# Arduino___case01.net
KiCad netlist of a schematic drawn in Altium Designer
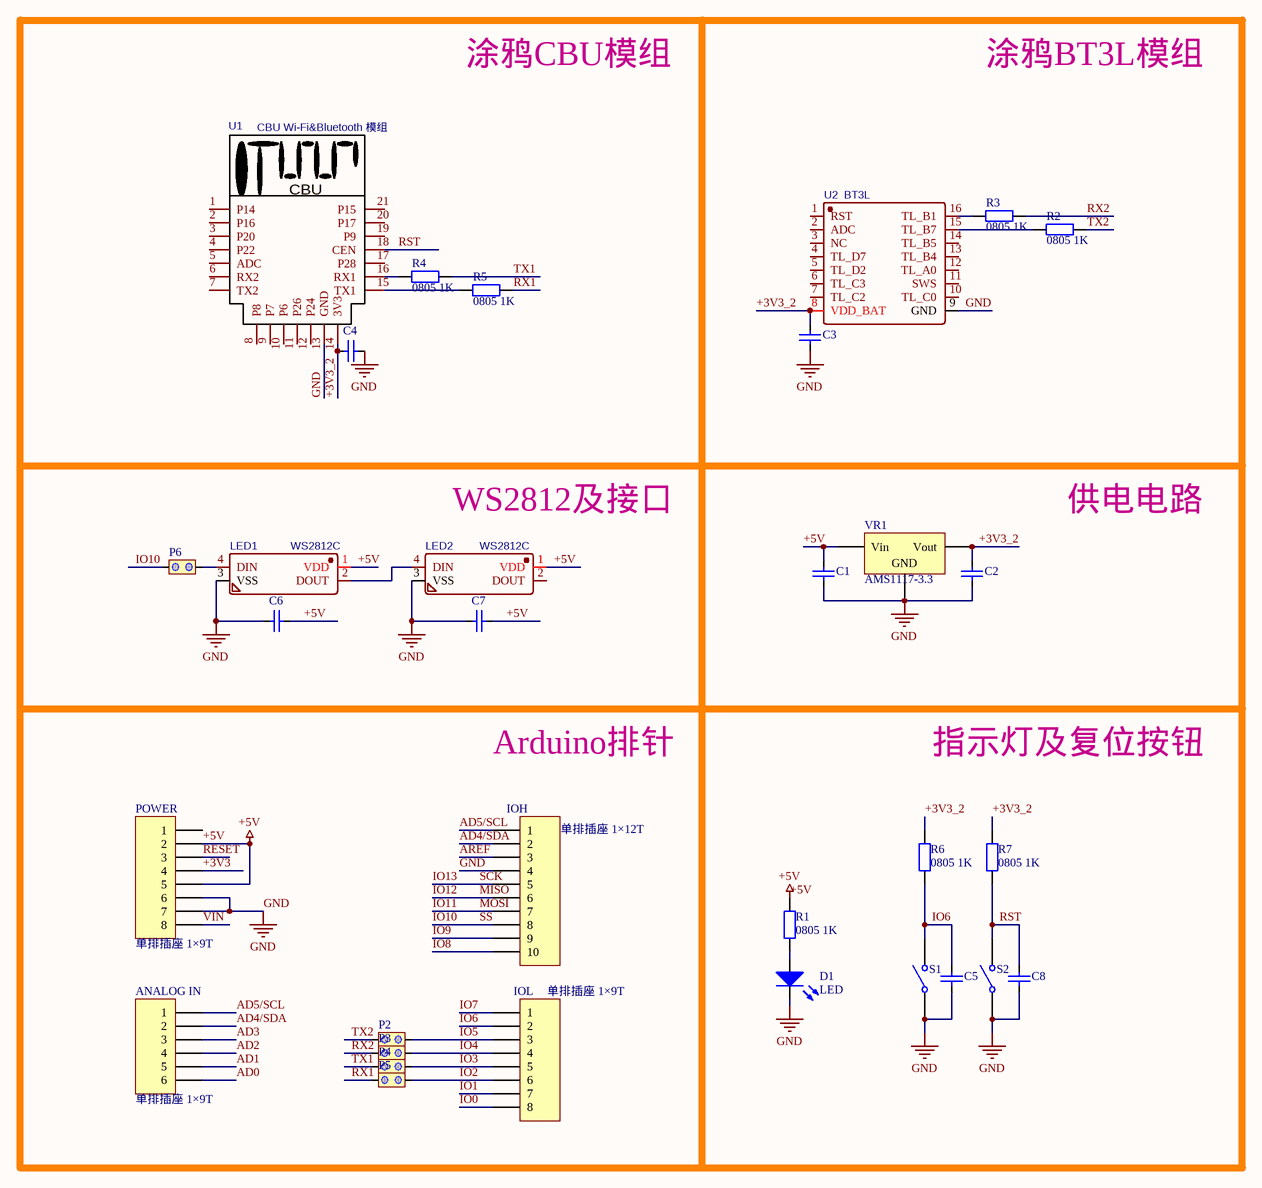
[diagram p0: Arduino_三明治开发板_case01.SchDoc]

(export (version "E")
  (design (tool "Eeschema 10.0.6"))
  (components
    (comp (ref "ANALOG IN")
      (value "单排插座 1×9T")
      (footprint "HDR1X6Z")
      (description "Header, 6-Pin")
      (fields (field (name "PUBLISHER") "Altium Limited"))
      (libsource (lib "Miscellaneous Connectors") (part "Header 6"))
    )
    (comp (ref "C1")
      (value "1206 0.1uF")
      (footprint "PcbLib1:0805-CAP-min")
      (description "Capacitor")
      (fields (field (name "PUBLISHER") "Altium Limited"))
      (libsource (lib "Cap_han") (part "Cap-1206"))
    )
    (comp (ref "C2")
      (value "1206 0.1uF")
      (footprint "PcbLib1:0805-CAP-min")
      (description "Capacitor")
      (fields (field (name "PUBLISHER") "Altium Limited"))
      (libsource (lib "Cap_han") (part "Cap-1206"))
    )
    (comp (ref "C3")
      (value "1206 0.1uF")
      (footprint "0805-CAP-min")
      (description "Capacitor")
      (fields (field (name "PUBLISHER") "Altium Limited"))
      (libsource (lib "Cap_han") (part "Cap-1206"))
    )
    (comp (ref "C4")
      (value "1206 0.1uF")
      (footprint "PcbLib1:0805-CAP-min")
      (description "Capacitor")
      (fields (field (name "PUBLISHER") "Altium Limited"))
      (libsource (lib "Cap_han") (part "Cap-1206"))
    )
    (comp (ref "C5")
      (value "1206 0.1uF")
      (footprint "PcbLib1:0805-CAP-min")
      (description "Capacitor")
      (fields (field (name "PUBLISHER") "Altium Limited"))
      (libsource (lib "Cap_han") (part "Cap-1206"))
    )
    (comp (ref "C6")
      (value "1206 0.1uF")
      (footprint "PcbLib1:0805-CAP-min")
      (description "Capacitor")
      (fields (field (name "PUBLISHER") "Altium Limited"))
      (libsource (lib "Cap_han") (part "Cap-1206"))
    )
    (comp (ref "C7")
      (value "1206 0.1uF")
      (footprint "PcbLib1:0805-CAP-min")
      (description "Capacitor")
      (fields (field (name "PUBLISHER") "Altium Limited"))
      (libsource (lib "Cap_han") (part "Cap-1206"))
    )
    (comp (ref "C8")
      (value "1206 0.1uF")
      (footprint "PcbLib1:0805-CAP-min")
      (description "Capacitor")
      (fields (field (name "PUBLISHER") "Altium Limited"))
      (libsource (lib "Cap_han") (part "Cap-1206"))
    )
    (comp (ref "D1")
      (value "LED")
      (footprint "PcbLib1:LED3014-FD")
      (fields (field (name "PUBLISHER") "Altium Limited"))
      (libsource (lib "LED_han") (part "LED-3014"))
    )
    (comp (ref "IOH")
      (value "单排插座 1×12T")
      (footprint "HDR1X10Z")
      (description "Header, 10-Pin")
      (fields (field (name "PUBLISHER") "Altium Limited"))
      (libsource (lib "Miscellaneous Connectors") (part "Header 10"))
    )
    (comp (ref "IOL")
      (value "单排插座 1×9T")
      (footprint "HDR1X8Z")
      (description "Header, 8-Pin")
      (fields (field (name "PUBLISHER") "Altium Limited"))
      (libsource (lib "Miscellaneous Connectors") (part "Header 8"))
    )
    (comp (ref "LED1")
      (value "WS2812C")
      (footprint "LED-SMD_4P-L5.0-W5.0-TL")
      (fields (field (name "BOM_SUPPLIER PART") "C114587") (field (name "CONTRIBUTOR") "LCSC"))
      (libsource (lib "altium-import") (part "root_2_WS2812C_"))
    )
    (comp (ref "LED2")
      (value "WS2812C")
      (footprint "LED-SMD_4P-L5.0-W5.0-TL")
      (fields (field (name "BOM_SUPPLIER PART") "C114587") (field (name "CONTRIBUTOR") "LCSC"))
      (libsource (lib "altium-import") (part "root_2_WS2812C_"))
    )
    (comp (ref "P2")
      (value "HDR1*2")
      (footprint "HDR1X2")
      (fields (field (name "PUBLISHER") "Altium Limited"))
      (libsource (lib "Connectors_han") (part "HDR1*2_2"))
    )
    (comp (ref "P3")
      (value "HDR1*2")
      (footprint "HDR1X2")
      (fields (field (name "PUBLISHER") "Altium Limited"))
      (libsource (lib "Connectors_han") (part "HDR1*2_2"))
    )
    (comp (ref "P4")
      (value "HDR1*2")
      (footprint "HDR1X2")
      (fields (field (name "PUBLISHER") "Altium Limited"))
      (libsource (lib "Connectors_han") (part "HDR1*2_2"))
    )
    (comp (ref "P5")
      (value "HDR1*2")
      (footprint "HDR1X2")
      (fields (field (name "PUBLISHER") "Altium Limited"))
      (libsource (lib "Connectors_han") (part "HDR1*2_2"))
    )
    (comp (ref "P6")
      (value "HDR1*2")
      (footprint "HDR1X2")
      (fields (field (name "PUBLISHER") "Altium Limited"))
      (libsource (lib "Connectors_han") (part "HDR1*2_2"))
    )
    (comp (ref "POWER")
      (value "单排插座 1×9T")
      (footprint "HDR1X8Z")
      (description "Header, 8-Pin")
      (fields (field (name "PUBLISHER") "Altium Limited"))
      (libsource (lib "") (part "Header 8_1"))
    )
    (comp (ref "R1")
      (value "0805 1K")
      (footprint "0805-R-min")
      (description "Resistor")
      (fields (field (name "PUBLISHER") "Altium Limited"))
      (libsource (lib "Resistance_han") (part "Res-0805"))
    )
    (comp (ref "R2")
      (value "0805 1K")
      (footprint "0805-R-min")
      (description "Resistor")
      (fields (field (name "PUBLISHER") "Altium Limited"))
      (libsource (lib "") (part "Res-0805_1"))
    )
    (comp (ref "R3")
      (value "0805 1K")
      (footprint "0805-R-min")
      (description "Resistor")
      (fields (field (name "PUBLISHER") "Altium Limited"))
      (libsource (lib "") (part "Res-0805_1"))
    )
    (comp (ref "R4")
      (value "0805 1K")
      (footprint "0805-R-min")
      (description "Resistor")
      (fields (field (name "PUBLISHER") "Altium Limited"))
      (libsource (lib "") (part "Res-0805_1"))
    )
    (comp (ref "R5")
      (value "0805 1K")
      (footprint "0805-R-min")
      (description "Resistor")
      (fields (field (name "PUBLISHER") "Altium Limited"))
      (libsource (lib "") (part "Res-0805_1"))
    )
    (comp (ref "R6")
      (value "0805 1K")
      (footprint "0805-R-min")
      (description "Resistor")
      (fields (field (name "PUBLISHER") "Altium Limited"))
      (libsource (lib "Resistance_han") (part "Res-0805"))
    )
    (comp (ref "R7")
      (value "0805 1K")
      (footprint "0805-R-min")
      (description "Resistor")
      (fields (field (name "PUBLISHER") "Altium Limited"))
      (libsource (lib "Resistance_han") (part "Res-0805"))
    )
    (comp (ref "S1")
      (value "SW-SPST")
      (footprint "Switch")
      (description "Single-Pole, Single-Throw Switch")
      (fields (field (name "PUBLISHER") "Altium Limited"))
      (libsource (lib "Miscellaneous Devices") (part "SW-SPST"))
    )
    (comp (ref "S2")
      (value "SW-SPST")
      (footprint "Switch")
      (description "Single-Pole, Single-Throw Switch")
      (fields (field (name "PUBLISHER") "Altium Limited"))
      (libsource (lib "Miscellaneous Devices") (part "SW-SPST"))
    )
    (comp (ref "U1")
      (value "CBU Wi-Fi&Bluetooth 模组")
      (footprint "PcbLib1:CBU WIFI&BLUETOOTH")
      (fields (field (name "BOM_MANUFACTURER PART") "SHOWNAME=F") (field (name "CONTRIBUTOR") "chenlf"))
      (libsource (lib "MCU_han") (part "CBU Wi-Fi&Bluetooth 模组"))
    )
    (comp (ref "U2")
      (value "BT3L")
      (footprint "PcbLib1:BLUETOOTH-SMD_16P-L24.0-W16.0-P2.0-BT3L")
      (fields (field (name "BOM_SUPPLIER PART") "C2828287") (field (name "CONTRIBUTOR") "LCSC"))
      (libsource (lib "altium-import") (part "root_0_mirrored_BT3L_"))
    )
    (comp (ref "VR1")
      (value "AMS1117-3.3")
      (footprint "SOT-223")
      (description "低压差线性稳压(LDO)")
      (libsource (lib "LDO") (part "SOT-223 AMS1117-3.3"))
    )
  )
  (nets
    (net (code "1") (name "+5V") (class "Default")
      (node (ref "C1") (pin "1") (pinfunction "1_1") (pintype "passive"))
      (node (ref "C6") (pin "1") (pinfunction "1_1") (pintype "passive"))
      (node (ref "C7") (pin "1") (pinfunction "1_1") (pintype "passive"))
      (node (ref "LED1") (pin "1") (pinfunction "VDD_1") (pintype "passive"))
      (node (ref "LED2") (pin "1") (pinfunction "VDD_1") (pintype "passive"))
      (node (ref "POWER") (pin "2") (pinfunction "2_2") (pintype "passive"))
      (node (ref "POWER") (pin "5") (pinfunction "5_5") (pintype "passive"))
      (node (ref "R1") (pin "1") (pinfunction "1_1") (pintype "passive"))
      (node (ref "VR1") (pin "3") (pinfunction "Vin_3") (pintype "passive"))
    )
    (net (code "2") (name "/+3V3") (class "Default")
      (node (ref "POWER") (pin "4") (pinfunction "4_4") (pintype "passive"))
    )
    (net (code "3") (name "/+3V3_2") (class "Default")
      (node (ref "C2") (pin "2") (pinfunction "2_2") (pintype "passive"))
      (node (ref "C3") (pin "2") (pinfunction "2_2") (pintype "passive"))
      (node (ref "C4") (pin "2") (pinfunction "2_2") (pintype "passive"))
      (node (ref "R6") (pin "1") (pinfunction "1_1") (pintype "passive"))
      (node (ref "R7") (pin "1") (pinfunction "1_1") (pintype "passive"))
      (node (ref "U1") (pin "14") (pinfunction "3V3_14") (pintype "passive"))
      (node (ref "U2") (pin "8") (pinfunction "VDD_BAT_8") (pintype "passive"))
      (node (ref "VR1") (pin "2") (pinfunction "Vout_2") (pintype "passive"))
    )
    (net (code "4") (name "/AD0") (class "Default")
      (node (ref "ANALOG IN") (pin "6") (pinfunction "6_6") (pintype "passive"))
    )
    (net (code "5") (name "/AD1") (class "Default")
      (node (ref "ANALOG IN") (pin "5") (pinfunction "5_5") (pintype "passive"))
    )
    (net (code "6") (name "/AD2") (class "Default")
      (node (ref "ANALOG IN") (pin "4") (pinfunction "4_4") (pintype "passive"))
    )
    (net (code "7") (name "/AD3") (class "Default")
      (node (ref "ANALOG IN") (pin "3") (pinfunction "3_3") (pintype "passive"))
    )
    (net (code "8") (name "/AD4{slash}SDA") (class "Default")
      (node (ref "ANALOG IN") (pin "2") (pinfunction "2_2") (pintype "passive"))
      (node (ref "IOH") (pin "2") (pinfunction "2_2") (pintype "passive"))
    )
    (net (code "9") (name "/AD5{slash}SCL") (class "Default")
      (node (ref "ANALOG IN") (pin "1") (pinfunction "1_1") (pintype "passive"))
      (node (ref "IOH") (pin "1") (pinfunction "1_1") (pintype "passive"))
    )
    (net (code "10") (name "/AREF") (class "Default")
      (node (ref "IOH") (pin "3") (pinfunction "3_3") (pintype "passive"))
    )
    (net (code "11") (name "/IO0") (class "Default")
      (node (ref "IOL") (pin "8") (pinfunction "8_8") (pintype "passive"))
    )
    (net (code "12") (name "/IO1") (class "Default")
      (node (ref "IOL") (pin "7") (pinfunction "7_7") (pintype "passive"))
    )
    (net (code "13") (name "/IO2") (class "Default")
      (node (ref "IOL") (pin "6") (pinfunction "6_6") (pintype "passive"))
      (node (ref "P5") (pin "2") (pinfunction "2_2") (pintype "passive"))
    )
    (net (code "14") (name "/IO3") (class "Default")
      (node (ref "IOL") (pin "5") (pinfunction "5_5") (pintype "passive"))
      (node (ref "P4") (pin "2") (pinfunction "2_2") (pintype "passive"))
    )
    (net (code "15") (name "/IO4") (class "Default")
      (node (ref "IOL") (pin "4") (pinfunction "4_4") (pintype "passive"))
      (node (ref "P3") (pin "2") (pinfunction "2_2") (pintype "passive"))
    )
    (net (code "16") (name "/IO5") (class "Default")
      (node (ref "IOL") (pin "3") (pinfunction "3_3") (pintype "passive"))
      (node (ref "P2") (pin "2") (pinfunction "2_2") (pintype "passive"))
    )
    (net (code "17") (name "/IO6") (class "Default")
      (node (ref "C5") (pin "1") (pinfunction "1_1") (pintype "passive"))
      (node (ref "IOL") (pin "2") (pinfunction "2_2") (pintype "passive"))
      (node (ref "R6") (pin "2") (pinfunction "2_2") (pintype "passive"))
      (node (ref "S1") (pin "2") (pinfunction "NO_2") (pintype "passive"))
    )
    (net (code "18") (name "/IO7") (class "Default")
      (node (ref "IOL") (pin "1") (pinfunction "1_1") (pintype "passive"))
    )
    (net (code "19") (name "/IO8") (class "Default")
      (node (ref "IOH") (pin "10") (pinfunction "10_10") (pintype "passive"))
    )
    (net (code "20") (name "/IO9") (class "Default")
      (node (ref "IOH") (pin "9") (pinfunction "9_9") (pintype "passive"))
    )
    (net (code "21") (name "/IO10") (class "Default")
      (node (ref "IOH") (pin "8") (pinfunction "8_8") (pintype "passive"))
      (node (ref "P6") (pin "1") (pinfunction "1_1") (pintype "passive"))
    )
    (net (code "22") (name "/IO11") (class "Default")
      (node (ref "IOH") (pin "7") (pinfunction "7_7") (pintype "passive"))
    )
    (net (code "23") (name "/IO12") (class "Default")
      (node (ref "IOH") (pin "6") (pinfunction "6_6") (pintype "passive"))
    )
    (net (code "24") (name "/IO13") (class "Default")
      (node (ref "IOH") (pin "5") (pinfunction "5_5") (pintype "passive"))
    )
    (net (code "25") (name "/RESET") (class "Default")
      (node (ref "POWER") (pin "3") (pinfunction "3_3") (pintype "passive"))
    )
    (net (code "26") (name "/RST") (class "Default")
      (node (ref "C8") (pin "1") (pinfunction "1_1") (pintype "passive"))
      (node (ref "R7") (pin "2") (pinfunction "2_2") (pintype "passive"))
      (node (ref "S2") (pin "2") (pinfunction "NO_2") (pintype "passive"))
      (node (ref "U1") (pin "18") (pinfunction "CEN_18") (pintype "passive"))
    )
    (net (code "27") (name "/RX1") (class "Default")
      (node (ref "P5") (pin "1") (pinfunction "1_1") (pintype "passive"))
      (node (ref "R5") (pin "1") (pinfunction "1_1") (pintype "passive"))
    )
    (net (code "28") (name "/RX2") (class "Default")
      (node (ref "P3") (pin "1") (pinfunction "1_1") (pintype "passive"))
      (node (ref "R3") (pin "1") (pinfunction "1_1") (pintype "passive"))
    )
    (net (code "29") (name "/TX1") (class "Default")
      (node (ref "P4") (pin "1") (pinfunction "1_1") (pintype "passive"))
      (node (ref "R4") (pin "1") (pinfunction "1_1") (pintype "passive"))
    )
    (net (code "30") (name "/TX2") (class "Default")
      (node (ref "P2") (pin "1") (pinfunction "1_1") (pintype "passive"))
      (node (ref "R2") (pin "1") (pinfunction "1_1") (pintype "passive"))
    )
    (net (code "31") (name "/VIN") (class "Default")
      (node (ref "POWER") (pin "8") (pinfunction "8_8") (pintype "passive"))
    )
    (net (code "32") (name "GND") (class "Default")
      (node (ref "C1") (pin "2") (pinfunction "2_2") (pintype "passive"))
      (node (ref "C2") (pin "1") (pinfunction "1_1") (pintype "passive"))
      (node (ref "C3") (pin "1") (pinfunction "1_1") (pintype "passive"))
      (node (ref "C4") (pin "1") (pinfunction "1_1") (pintype "passive"))
      (node (ref "C5") (pin "2") (pinfunction "2_2") (pintype "passive"))
      (node (ref "C6") (pin "2") (pinfunction "2_2") (pintype "passive"))
      (node (ref "C7") (pin "2") (pinfunction "2_2") (pintype "passive"))
      (node (ref "C8") (pin "2") (pinfunction "2_2") (pintype "passive"))
      (node (ref "D1") (pin "2") (pinfunction "K_2") (pintype "passive"))
      (node (ref "IOH") (pin "4") (pinfunction "4_4") (pintype "passive"))
      (node (ref "LED1") (pin "3") (pinfunction "VSS_3") (pintype "passive"))
      (node (ref "LED2") (pin "3") (pinfunction "VSS_3") (pintype "passive"))
      (node (ref "POWER") (pin "6") (pinfunction "6_6") (pintype "passive"))
      (node (ref "POWER") (pin "7") (pinfunction "7_7") (pintype "passive"))
      (node (ref "S1") (pin "1") (pinfunction "COMMON_1") (pintype "passive"))
      (node (ref "S2") (pin "1") (pinfunction "COMMON_1") (pintype "passive"))
      (node (ref "U1") (pin "13") (pinfunction "GND_13") (pintype "passive"))
      (node (ref "U2") (pin "9") (pinfunction "GND_9") (pintype "passive"))
      (node (ref "VR1") (pin "1") (pinfunction "GND_1") (pintype "passive"))
    )
    (net (code "33") (name "Net-(D1-A)") (class "Default")
      (node (ref "D1") (pin "1") (pinfunction "A_1") (pintype "passive"))
      (node (ref "R1") (pin "2") (pinfunction "2_2") (pintype "passive"))
    )
    (net (code "34") (name "Net-(LED1-DIN)") (class "Default")
      (node (ref "LED1") (pin "4") (pinfunction "DIN_4") (pintype "passive"))
      (node (ref "P6") (pin "2") (pinfunction "2_2") (pintype "passive"))
    )
    (net (code "35") (name "Net-(LED1-DOUT)") (class "Default")
      (node (ref "LED1") (pin "2") (pinfunction "DOUT_2") (pintype "passive"))
      (node (ref "LED2") (pin "4") (pinfunction "DIN_4") (pintype "passive"))
    )
    (net (code "36") (name "Net-(U1-RX1)") (class "Default")
      (node (ref "R4") (pin "2") (pinfunction "2_2") (pintype "passive"))
      (node (ref "U1") (pin "16") (pinfunction "RX1_16") (pintype "passive"))
    )
    (net (code "37") (name "Net-(U1-TX1)") (class "Default")
      (node (ref "R5") (pin "2") (pinfunction "2_2") (pintype "passive"))
      (node (ref "U1") (pin "15") (pinfunction "TX1_15") (pintype "passive"))
    )
    (net (code "38") (name "Net-(U2-TL_B1)") (class "Default")
      (node (ref "R3") (pin "2") (pinfunction "2_2") (pintype "passive"))
      (node (ref "U2") (pin "16") (pinfunction "TL_B1_16") (pintype "passive"))
    )
    (net (code "39") (name "Net-(U2-TL_B7)") (class "Default")
      (node (ref "R2") (pin "2") (pinfunction "2_2") (pintype "passive"))
      (node (ref "U2") (pin "15") (pinfunction "TL_B7_15") (pintype "passive"))
    )
    (net (code "40") (name "unconnected-(LED2-DOUT-Pad2)") (class "Default")
      (node (ref "LED2") (pin "2") (pinfunction "DOUT_2") (pintype "passive"))
    )
    (net (code "41") (name "unconnected-(POWER-Pad1)") (class "Default")
      (node (ref "POWER") (pin "1") (pinfunction "1_1") (pintype "passive"))
    )
    (net (code "42") (name "unconnected-(U1-ADC-Pad5)") (class "Default")
      (node (ref "U1") (pin "5") (pinfunction "ADC_5") (pintype "passive"))
    )
    (net (code "43") (name "unconnected-(U1-P6-Pad10)") (class "Default")
      (node (ref "U1") (pin "10") (pinfunction "P6_10") (pintype "passive"))
    )
    (net (code "44") (name "unconnected-(U1-P7-Pad9)") (class "Default")
      (node (ref "U1") (pin "9") (pinfunction "P7_9") (pintype "passive"))
    )
    (net (code "45") (name "unconnected-(U1-P8-Pad8)") (class "Default")
      (node (ref "U1") (pin "8") (pinfunction "P8_8") (pintype "passive"))
    )
    (net (code "46") (name "unconnected-(U1-P9-Pad19)") (class "Default")
      (node (ref "U1") (pin "19") (pinfunction "P9_19") (pintype "passive"))
    )
    (net (code "47") (name "unconnected-(U1-P14-Pad1)") (class "Default")
      (node (ref "U1") (pin "1") (pinfunction "P14_1") (pintype "passive"))
    )
    (net (code "48") (name "unconnected-(U1-P15-Pad21)") (class "Default")
      (node (ref "U1") (pin "21") (pinfunction "P15_21") (pintype "passive"))
    )
    (net (code "49") (name "unconnected-(U1-P16-Pad2)") (class "Default")
      (node (ref "U1") (pin "2") (pinfunction "P16_2") (pintype "passive"))
    )
    (net (code "50") (name "unconnected-(U1-P17-Pad20)") (class "Default")
      (node (ref "U1") (pin "20") (pinfunction "P17_20") (pintype "passive"))
    )
    (net (code "51") (name "unconnected-(U1-P20-Pad3)") (class "Default")
      (node (ref "U1") (pin "3") (pinfunction "P20_3") (pintype "passive"))
    )
    (net (code "52") (name "unconnected-(U1-P22-Pad4)") (class "Default")
      (node (ref "U1") (pin "4") (pinfunction "P22_4") (pintype "passive"))
    )
    (net (code "53") (name "unconnected-(U1-P24-Pad12)") (class "Default")
      (node (ref "U1") (pin "12") (pinfunction "P24_12") (pintype "passive"))
    )
    (net (code "54") (name "unconnected-(U1-P26-Pad11)") (class "Default")
      (node (ref "U1") (pin "11") (pinfunction "P26_11") (pintype "passive"))
    )
    (net (code "55") (name "unconnected-(U1-P28-Pad17)") (class "Default")
      (node (ref "U1") (pin "17") (pinfunction "P28_17") (pintype "passive"))
    )
    (net (code "56") (name "unconnected-(U1-RX2-Pad6)") (class "Default")
      (node (ref "U1") (pin "6") (pinfunction "RX2_6") (pintype "passive"))
    )
    (net (code "57") (name "unconnected-(U1-TX2-Pad7)") (class "Default")
      (node (ref "U1") (pin "7") (pinfunction "TX2_7") (pintype "passive"))
    )
    (net (code "58") (name "unconnected-(U2-ADC-Pad2)") (class "Default")
      (node (ref "U2") (pin "2") (pinfunction "ADC_2") (pintype "passive"))
    )
    (net (code "59") (name "unconnected-(U2-NC-Pad3)") (class "Default")
      (node (ref "U2") (pin "3") (pinfunction "NC_3") (pintype "passive"))
    )
    (net (code "60") (name "unconnected-(U2-RST-Pad1)") (class "Default")
      (node (ref "U2") (pin "1") (pinfunction "RST_1") (pintype "passive"))
    )
    (net (code "61") (name "unconnected-(U2-SWS-Pad11)") (class "Default")
      (node (ref "U2") (pin "11") (pinfunction "SWS_11") (pintype "passive"))
    )
    (net (code "62") (name "unconnected-(U2-TL_A0-Pad12)") (class "Default")
      (node (ref "U2") (pin "12") (pinfunction "TL_A0_12") (pintype "passive"))
    )
    (net (code "63") (name "unconnected-(U2-TL_B4-Pad13)") (class "Default")
      (node (ref "U2") (pin "13") (pinfunction "TL_B4_13") (pintype "passive"))
    )
    (net (code "64") (name "unconnected-(U2-TL_B5-Pad14)") (class "Default")
      (node (ref "U2") (pin "14") (pinfunction "TL_B5_14") (pintype "passive"))
    )
    (net (code "65") (name "unconnected-(U2-TL_C0-Pad10)") (class "Default")
      (node (ref "U2") (pin "10") (pinfunction "TL_C0_10") (pintype "passive"))
    )
    (net (code "66") (name "unconnected-(U2-TL_C2-Pad7)") (class "Default")
      (node (ref "U2") (pin "7") (pinfunction "TL_C2_7") (pintype "passive"))
    )
    (net (code "67") (name "unconnected-(U2-TL_C3-Pad6)") (class "Default")
      (node (ref "U2") (pin "6") (pinfunction "TL_C3_6") (pintype "passive"))
    )
    (net (code "68") (name "unconnected-(U2-TL_D2-Pad5)") (class "Default")
      (node (ref "U2") (pin "5") (pinfunction "TL_D2_5") (pintype "passive"))
    )
    (net (code "69") (name "unconnected-(U2-TL_D7-Pad4)") (class "Default")
      (node (ref "U2") (pin "4") (pinfunction "TL_D7_4") (pintype "passive"))
    )
  )
)
